# FDCAN.net
KiCad netlist of a schematic drawn in Altium Designer
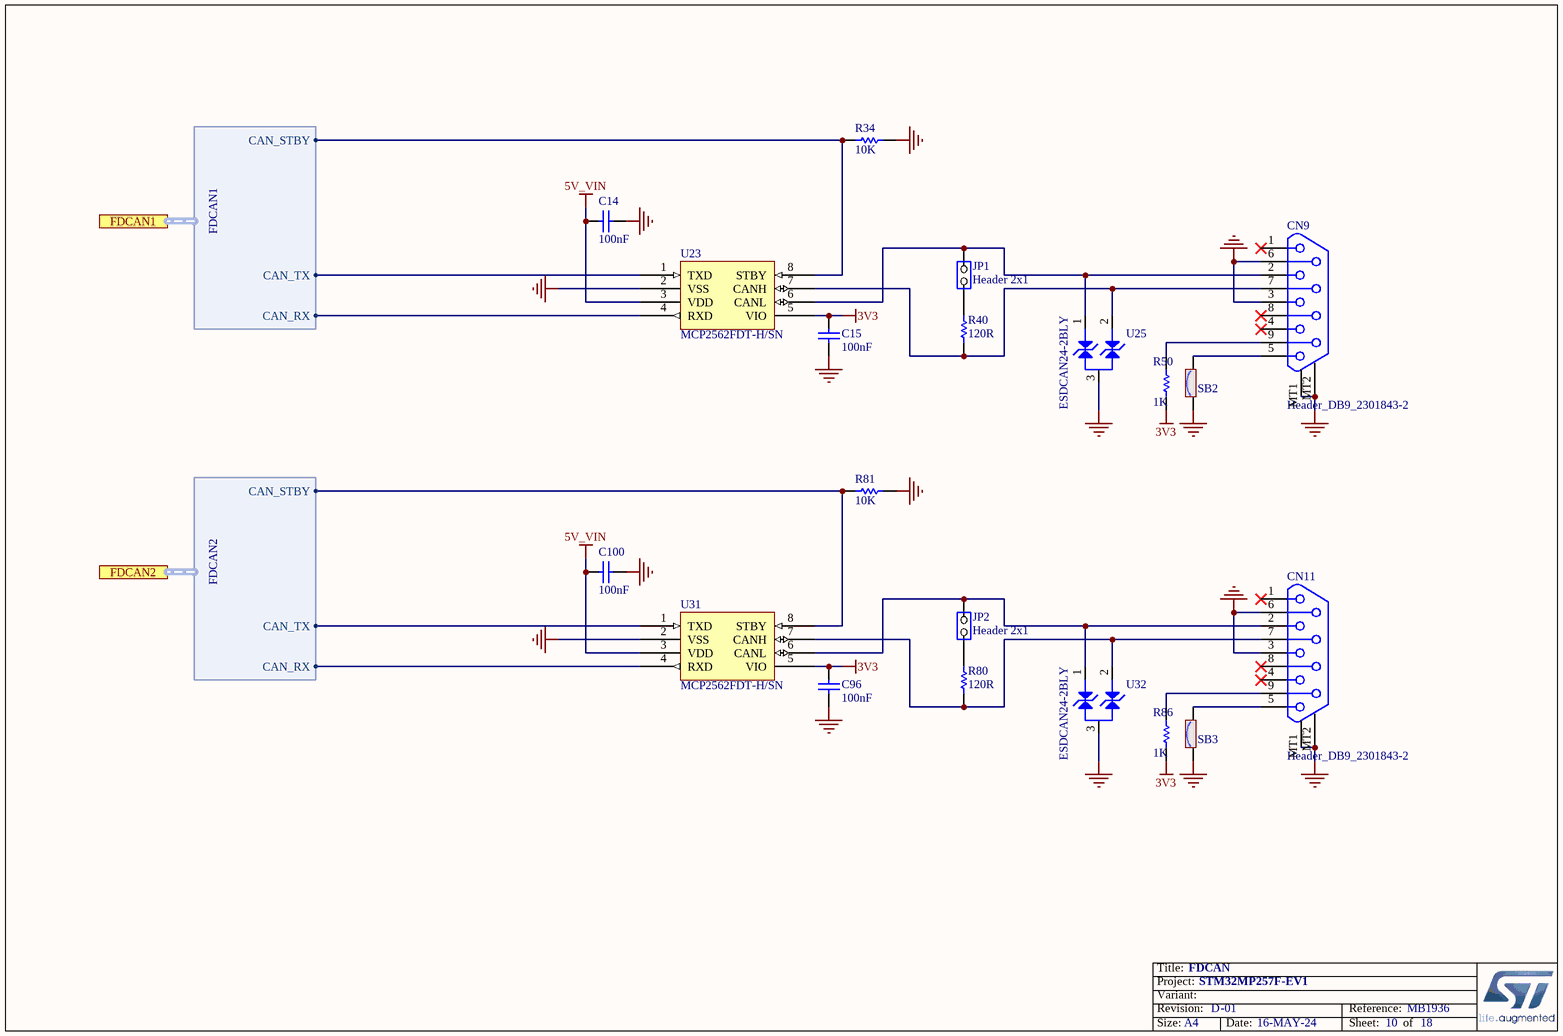
[diagram p0: FDCAN.SchDoc]

(export (version "E")
  (design (tool "Eeschema 10.0.6"))
  (components
    (comp (ref "C14")
      (value "100nF")
      (footprint "MCD_PARTS:C0402")
      (description "Capacitor, MLCC, 100nF, 16V, X7R, +/-10%, 0402, T=0.5mm")
      (fields (field (name "INTERNAL_PART_NUMBER") "MCD-00006") (field (name "MANUFACTURER") "YAGEO"))
      (libsource (lib "MCD_PARTS_database") (part "Capacitor"))
    )
    (comp (ref "C15")
      (value "100nF")
      (footprint "MCD_PARTS:C0402")
      (description "Capacitor, MLCC, 100nF, 16V, X7R, +/-10%, 0402, T=0.5mm")
      (fields (field (name "INTERNAL_PART_NUMBER") "MCD-00006") (field (name "MANUFACTURER") "YAGEO"))
      (libsource (lib "MCD_PARTS_database") (part "Capacitor"))
    )
    (comp (ref "C96")
      (value "100nF")
      (footprint "MCD_PARTS:C0402")
      (description "Capacitor, MLCC, 100nF, 16V, X7R, +/-10%, 0402, T=0.5mm")
      (fields (field (name "INTERNAL_PART_NUMBER") "MCD-00006") (field (name "MANUFACTURER") "YAGEO"))
      (libsource (lib "MCD_PARTS_database") (part "Capacitor"))
    )
    (comp (ref "C100")
      (value "100nF")
      (footprint "MCD_PARTS:C0402")
      (description "Capacitor, MLCC, 100nF, 16V, X7R, +/-10%, 0402, T=0.5mm")
      (fields (field (name "INTERNAL_PART_NUMBER") "MCD-00006") (field (name "MANUFACTURER") "YAGEO"))
      (libsource (lib "MCD_PARTS_database") (part "Capacitor"))
    )
    (comp (ref "CN9")
      (value "Header_DB9_2301843-2")
      (footprint "MCD_PARTS:CON_DB9-MALE_TYCO_2301843-2")
      (description "Connector_DB9-Male, 9pins, 1.39mm, RA, TH, T= 13.575mm/3.8mm")
      (fields
        (field (name "INTERNAL_PART_NUMBER") "MCD-01978")
        (field (name "MANUFACTURER") "TE CONNECTIVITY")
      )
      (libsource (lib "MCD_PARTS_database") (part "DB9_Header_male_2301843-2"))
    )
    (comp (ref "CN11")
      (value "Header_DB9_2301843-2")
      (footprint "MCD_PARTS:CON_DB9-MALE_TYCO_2301843-2")
      (description "Connector_DB9-Male, 9pins, 1.39mm, RA, TH, T= 13.575mm/3.8mm")
      (fields
        (field (name "INTERNAL_PART_NUMBER") "MCD-01978")
        (field (name "MANUFACTURER") "TE CONNECTIVITY")
      )
      (libsource (lib "MCD_PARTS_database") (part "DB9_Header_male_2301843-2"))
    )
    (comp (ref "JP1")
      (value "Header 2x1")
      (footprint "MCD_PARTS:CON_SAMTEC_TSW-102-07-G-S")
      (description "Header, 2x1, 2,54mm, VR, TH, Height 5.84mm/2.54mm")
      (fields
        (field (name "INTERNAL_PART_NUMBER") "MCD-00045")
        (field (name "MANUFACTURER_PART_NUMBER") "TSW-102-07-G-S")
        (field (name "PROVIDED_BY") "SUBCO")
      )
      (libsource (lib "MCD_PARTS_database") (part "Jumper_Header 2x1"))
    )
    (comp (ref "JP2")
      (value "Header 2x1")
      (footprint "MCD_PARTS:CON_SAMTEC_TSW-102-07-G-S")
      (description "Header, 2x1, 2,54mm, VR, TH, Height 5.84mm/2.54mm")
      (fields
        (field (name "INTERNAL_PART_NUMBER") "MCD-00045")
        (field (name "MANUFACTURER_PART_NUMBER") "TSW-102-07-G-S")
        (field (name "PROVIDED_BY") "SUBCO")
      )
      (libsource (lib "MCD_PARTS_database") (part "Jumper_Header 2x1"))
    )
    (comp (ref "R34")
      (value "10K")
      (footprint "MCD_PARTS:R0402")
      (description "Resistor,10K,0402,1%,1/16W")
      (fields
        (field (name "INTERNAL_PART_NUMBER") "MCD-00053")
        (field (name "MANUFACTURER_PART_NUMBER") "RC0402FR-0710KL")
        (field (name "PROVIDED_BY") "SUBCO")
      )
      (libsource (lib "MCD_PARTS_database") (part "Resistor"))
    )
    (comp (ref "R40")
      (value "120R")
      (footprint "MCD_PARTS:R0402")
      (description "Resistor, 120R, 0402, +/-1%, 1/16W")
      (fields (field (name "INTERNAL_PART_NUMBER") "MCD-00194") (field (name "MANUFACTURER") "YAGEO"))
      (libsource (lib "MCD_PARTS_database") (part "Resistor"))
    )
    (comp (ref "R50")
      (value "1K")
      (footprint "MCD_PARTS:R0402")
      (description "Resistor,1K,0402,1%,1/16W")
      (fields
        (field (name "INTERNAL_PART_NUMBER") "MCD-00061")
        (field (name "MANUFACTURER_PART_NUMBER") "RC0402FR-071KL")
        (field (name "PROVIDED_BY") "SUBCO")
      )
      (libsource (lib "MCD_PARTS_database") (part "Resistor"))
    )
    (comp (ref "R80")
      (value "120R")
      (footprint "MCD_PARTS:R0402")
      (description "Resistor, 120R, 0402, +/-1%, 1/16W")
      (fields (field (name "INTERNAL_PART_NUMBER") "MCD-00194") (field (name "MANUFACTURER") "YAGEO"))
      (libsource (lib "MCD_PARTS_database") (part "Resistor"))
    )
    (comp (ref "R81")
      (value "10K")
      (footprint "MCD_PARTS:R0402")
      (description "Resistor,10K,0402,1%,1/16W")
      (fields
        (field (name "INTERNAL_PART_NUMBER") "MCD-00053")
        (field (name "MANUFACTURER_PART_NUMBER") "RC0402FR-0710KL")
        (field (name "PROVIDED_BY") "SUBCO")
      )
      (libsource (lib "MCD_PARTS_database") (part "Resistor"))
    )
    (comp (ref "R86")
      (value "1K")
      (footprint "MCD_PARTS:R0402")
      (description "Resistor,1K,0402,1%,1/16W")
      (fields
        (field (name "INTERNAL_PART_NUMBER") "MCD-00061")
        (field (name "MANUFACTURER_PART_NUMBER") "RC0402FR-071KL")
        (field (name "PROVIDED_BY") "SUBCO")
      )
      (libsource (lib "MCD_PARTS_database") (part "Resistor"))
    )
    (comp (ref "SB2")
      (value "SB_ON")
      (footprint "MCD_PARTS:SOLDER-BRIDGE_R0402-0R")
      (description "Solder Bridge 0402 ON")
      (fields
        (field (name "INTERNAL_PART_NUMBER") "MCD-01618")
        (field (name "MANUFACTURER_PART_NUMBER") "RC0402JR-070RL")
        (field (name "PROVIDED_BY") "SUBCO")
      )
      (libsource (lib "MCD_PARTS_database") (part "SB_ON"))
    )
    (comp (ref "SB3")
      (value "SB_ON")
      (footprint "MCD_PARTS:SOLDER-BRIDGE_R0402-0R")
      (description "Solder Bridge 0402 ON")
      (fields
        (field (name "INTERNAL_PART_NUMBER") "MCD-01618")
        (field (name "MANUFACTURER_PART_NUMBER") "RC0402JR-070RL")
        (field (name "PROVIDED_BY") "SUBCO")
      )
      (libsource (lib "MCD_PARTS_database") (part "SB_ON"))
    )
    (comp (ref "U23")
      (value "MCP2562FDT-H/SN")
      (footprint "MCD_PARTS:ICC_SO8_5X4_P127")
      (description "High-Speed CAN Flexible Data Rate Transceiver")
      (fields
        (field (name "INTERNAL_PART_NUMBER") "MCD-00129")
        (field (name "MANUFACTURER") "MICROCHIP")
        (field (name "PROVIDED_BY") "SUBCO")
      )
      (libsource (lib "MCD_PARTS_database") (part "MCP2562FD"))
    )
    (comp (ref "U25")
      (value "ESDCAN24-2BLY")
      (footprint "MCD_PARTS:ESD_SOT23")
      (description "Automotive dual-line Transil. ESD CAN")
      (fields
        (field (name "INTERNAL_PART_NUMBER") "MCD-00143")
        (field (name "MANUFACTURER") "STMICROELECTRONICS")
        (field (name "PROVIDED_BY") "SUBCO with ST control")
      )
      (libsource (lib "MCD_PARTS_database") (part "ESD-TRANSIL-DUAL-BIDIR"))
    )
    (comp (ref "U31")
      (value "MCP2562FDT-H/SN")
      (footprint "MCD_PARTS:ICC_SO8_5X4_P127")
      (description "High-Speed CAN Flexible Data Rate Transceiver")
      (fields
        (field (name "INTERNAL_PART_NUMBER") "MCD-00129")
        (field (name "MANUFACTURER") "MICROCHIP")
        (field (name "PROVIDED_BY") "SUBCO")
      )
      (libsource (lib "MCD_PARTS_database") (part "MCP2562FD"))
    )
    (comp (ref "U32")
      (value "ESDCAN24-2BLY")
      (footprint "MCD_PARTS:ESD_SOT23")
      (description "Automotive dual-line Transil. ESD CAN")
      (fields
        (field (name "INTERNAL_PART_NUMBER") "MCD-00143")
        (field (name "MANUFACTURER") "STMICROELECTRONICS")
        (field (name "PROVIDED_BY") "SUBCO with ST control")
      )
      (libsource (lib "MCD_PARTS_database") (part "ESD-TRANSIL-DUAL-BIDIR"))
    )
  )
  (nets
    (net (code "5") (name "3V3") (class "Default")
      (node (ref "C15") (pin "2") (pinfunction "2_2") (pintype "passive"))
      (node (ref "C96") (pin "2") (pinfunction "2_2") (pintype "passive"))
      (node (ref "R50") (pin "1") (pinfunction "1_1") (pintype "passive"))
      (node (ref "R86") (pin "1") (pinfunction "1_1") (pintype "passive"))
      (node (ref "U23") (pin "5") (pinfunction "VIO_5") (pintype "power_in"))
      (node (ref "U31") (pin "5") (pinfunction "VIO_5") (pintype "power_in"))
    )
    (net (code "6") (name "5V_VIN") (class "Default")
      (node (ref "C100") (pin "1") (pinfunction "1_1") (pintype "passive"))
      (node (ref "C14") (pin "1") (pinfunction "1_1") (pintype "passive"))
      (node (ref "U23") (pin "3") (pinfunction "VDD_3") (pintype "power_in"))
      (node (ref "U31") (pin "3") (pinfunction "VDD_3") (pintype "power_in"))
    )
    (net (code "7") (name "GND") (class "Default")
      (node (ref "C100") (pin "2") (pinfunction "2_2") (pintype "passive"))
      (node (ref "C14") (pin "2") (pinfunction "2_2") (pintype "passive"))
      (node (ref "C15") (pin "1") (pinfunction "1_1") (pintype "passive"))
      (node (ref "C96") (pin "1") (pinfunction "1_1") (pintype "passive"))
      (node (ref "CN11") (pin "3") (pintype "passive"))
      (node (ref "CN11") (pin "6") (pintype "passive"))
      (node (ref "CN11") (pin "MT1") (pintype "passive"))
      (node (ref "CN11") (pin "MT2") (pintype "passive"))
      (node (ref "CN9") (pin "3") (pintype "passive"))
      (node (ref "CN9") (pin "6") (pintype "passive"))
      (node (ref "CN9") (pin "MT1") (pintype "passive"))
      (node (ref "CN9") (pin "MT2") (pintype "passive"))
      (node (ref "R34") (pin "2") (pinfunction "2_2") (pintype "passive"))
      (node (ref "R81") (pin "2") (pinfunction "2_2") (pintype "passive"))
      (node (ref "SB2") (pin "1") (pinfunction "1_1") (pintype "passive"))
      (node (ref "SB3") (pin "1") (pinfunction "1_1") (pintype "passive"))
      (node (ref "U23") (pin "2") (pinfunction "VSS_2") (pintype "power_in"))
      (node (ref "U25") (pin "3") (pintype "passive"))
      (node (ref "U31") (pin "2") (pinfunction "VSS_2") (pintype "power_in"))
      (node (ref "U32") (pin "3") (pintype "passive"))
    )
    (net (code "8") (name "Net-(CN9-Pad5)") (class "Default")
      (node (ref "CN9") (pin "5") (pintype "passive"))
      (node (ref "SB2") (pin "2") (pinfunction "2_2") (pintype "passive"))
    )
    (net (code "9") (name "Net-(CN9-Pad9)") (class "Default")
      (node (ref "CN9") (pin "9") (pintype "passive"))
      (node (ref "R50") (pin "2") (pinfunction "2_2") (pintype "passive"))
    )
    (net (code "10") (name "Net-(CN11-Pad5)") (class "Default")
      (node (ref "CN11") (pin "5") (pintype "passive"))
      (node (ref "SB3") (pin "2") (pinfunction "2_2") (pintype "passive"))
    )
    (net (code "11") (name "Net-(CN11-Pad9)") (class "Default")
      (node (ref "CN11") (pin "9") (pintype "passive"))
      (node (ref "R86") (pin "2") (pinfunction "2_2") (pintype "passive"))
    )
    (net (code "12") (name "Net-(JP1-COMMON)") (class "Default")
      (node (ref "JP1") (pin "1") (pinfunction "COMMON_1") (pintype "passive"))
      (node (ref "R40") (pin "2") (pinfunction "2_2") (pintype "passive"))
    )
    (net (code "13") (name "Net-(JP1-NO)") (class "Default")
      (node (ref "CN9") (pin "2") (pintype "passive"))
      (node (ref "JP1") (pin "2") (pinfunction "NO_2") (pintype "passive"))
      (node (ref "U23") (pin "6") (pinfunction "CANL_6") (pintype "bidirectional"))
      (node (ref "U25") (pin "1") (pintype "passive"))
    )
    (net (code "14") (name "Net-(JP2-COMMON)") (class "Default")
      (node (ref "JP2") (pin "1") (pinfunction "COMMON_1") (pintype "passive"))
      (node (ref "R80") (pin "2") (pinfunction "2_2") (pintype "passive"))
    )
    (net (code "15") (name "Net-(JP2-NO)") (class "Default")
      (node (ref "CN11") (pin "2") (pintype "passive"))
      (node (ref "JP2") (pin "2") (pinfunction "NO_2") (pintype "passive"))
      (node (ref "U31") (pin "6") (pinfunction "CANL_6") (pintype "bidirectional"))
      (node (ref "U32") (pin "1") (pintype "passive"))
    )
    (net (code "16") (name "Net-(U23-CANH)") (class "Default")
      (node (ref "CN9") (pin "7") (pintype "passive"))
      (node (ref "R40") (pin "1") (pinfunction "1_1") (pintype "passive"))
      (node (ref "U23") (pin "7") (pinfunction "CANH_7") (pintype "bidirectional"))
      (node (ref "U25") (pin "2") (pintype "passive"))
    )
    (net (code "17") (name "Net-(U23-STBY)") (class "Default")
      (node (ref "R34") (pin "1") (pinfunction "1_1") (pintype "passive"))
      (node (ref "U23") (pin "8") (pinfunction "STBY_8") (pintype "input"))
    )
    (net (code "18") (name "Net-(U31-CANH)") (class "Default")
      (node (ref "CN11") (pin "7") (pintype "passive"))
      (node (ref "R80") (pin "1") (pinfunction "1_1") (pintype "passive"))
      (node (ref "U31") (pin "7") (pinfunction "CANH_7") (pintype "bidirectional"))
      (node (ref "U32") (pin "2") (pintype "passive"))
    )
    (net (code "19") (name "Net-(U31-STBY)") (class "Default")
      (node (ref "R81") (pin "1") (pinfunction "1_1") (pintype "passive"))
      (node (ref "U31") (pin "8") (pinfunction "STBY_8") (pintype "input"))
    )
    (net (code "20") (name "unconnected-(CN9-Pad1)") (class "Default")
      (node (ref "CN9") (pin "1") (pintype "passive+no_connect"))
    )
    (net (code "21") (name "unconnected-(CN9-Pad4)") (class "Default")
      (node (ref "CN9") (pin "4") (pintype "passive+no_connect"))
    )
    (net (code "22") (name "unconnected-(CN9-Pad8)") (class "Default")
      (node (ref "CN9") (pin "8") (pintype "passive+no_connect"))
    )
    (net (code "23") (name "unconnected-(CN11-Pad1)") (class "Default")
      (node (ref "CN11") (pin "1") (pintype "passive+no_connect"))
    )
    (net (code "24") (name "unconnected-(CN11-Pad4)") (class "Default")
      (node (ref "CN11") (pin "4") (pintype "passive+no_connect"))
    )
    (net (code "25") (name "unconnected-(CN11-Pad8)") (class "Default")
      (node (ref "CN11") (pin "8") (pintype "passive+no_connect"))
    )
    (net (code "26") (name "unconnected-(U23-RXD-Pad4)") (class "Default")
      (node (ref "U23") (pin "4") (pinfunction "RXD_4") (pintype "output"))
    )
    (net (code "27") (name "unconnected-(U23-TXD-Pad1)") (class "Default")
      (node (ref "U23") (pin "1") (pinfunction "TXD_1") (pintype "input"))
    )
    (net (code "28") (name "unconnected-(U31-RXD-Pad4)") (class "Default")
      (node (ref "U31") (pin "4") (pinfunction "RXD_4") (pintype "output"))
    )
    (net (code "29") (name "unconnected-(U31-TXD-Pad1)") (class "Default")
      (node (ref "U31") (pin "1") (pinfunction "TXD_1") (pintype "input"))
    )
  )
)
